# R1250GSA_Foglamp_Swith.net
KiCad netlist of a schematic drawn in Altium Designer
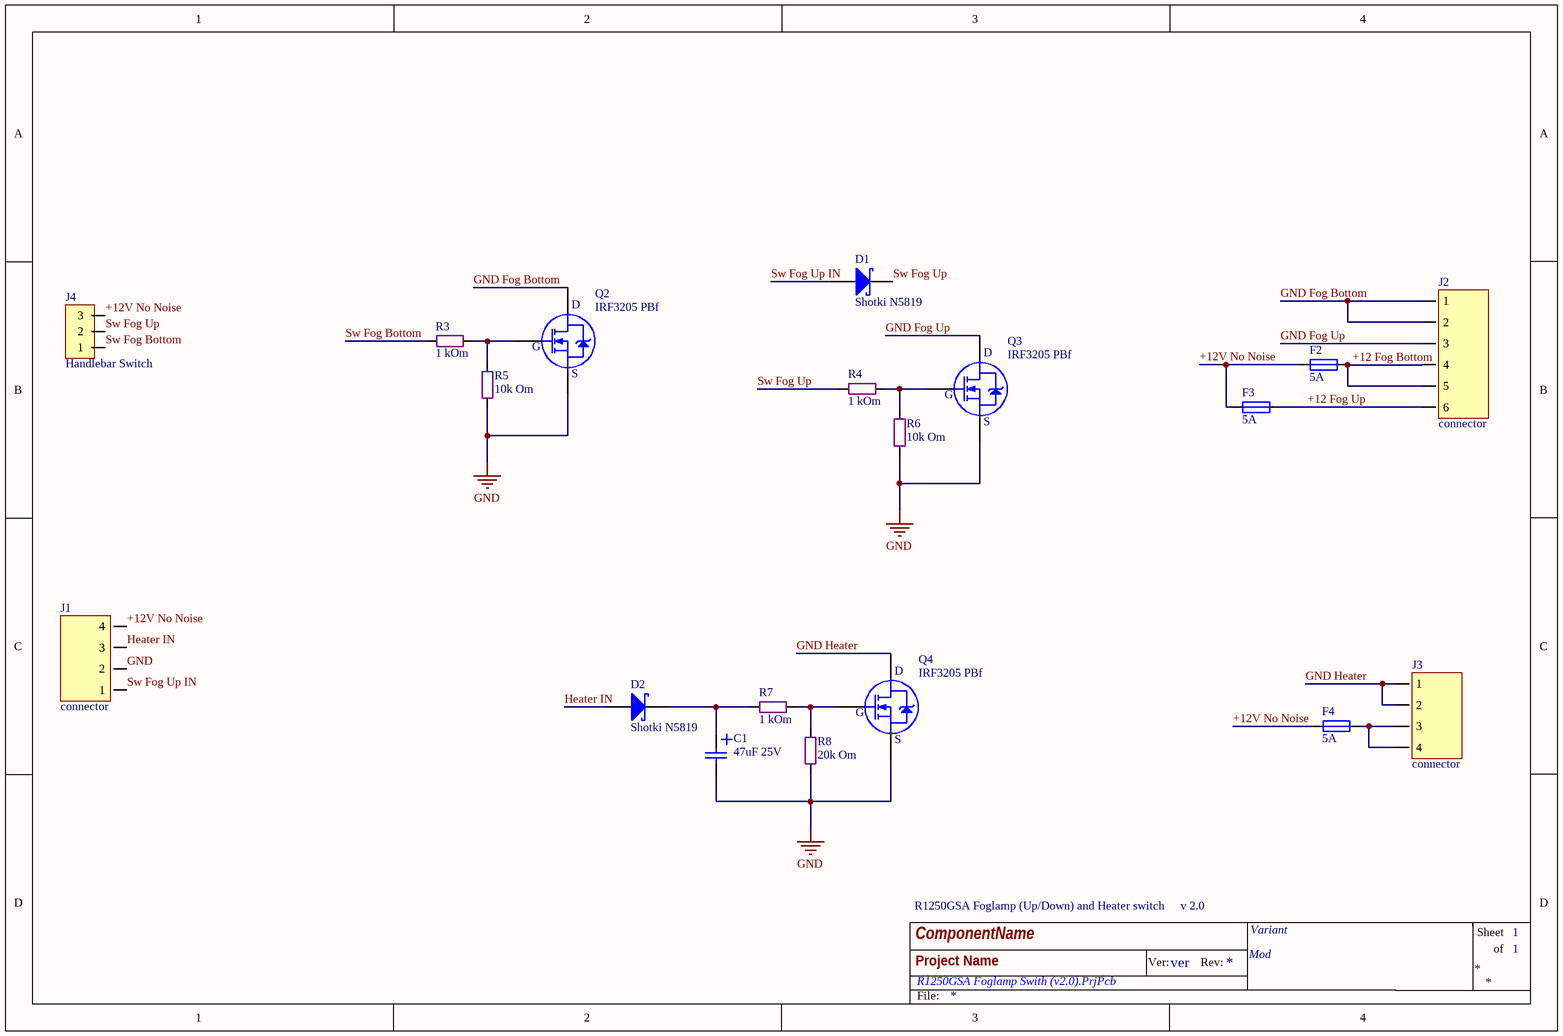
[diagram p0: R1250GSA Foglamp Swith (v2.0).SchDoc]

(export (version "E")
  (design (tool "Eeschema 10.0.6"))
  (components
    (comp (ref "C1")
      (value "47uF 25V")
      (footprint "Capacitor:Cap E p2mm D6.5xH11")
      (description "Capacitor")
      (libsource (lib "Capacitor") (part "Cap Elecrolitic"))
    )
    (comp (ref "D1")
      (value "Shotki N5819")
      (footprint "Diodes:Diode DO-41")
      (description "Shotki  Diode")
      (libsource (lib "Diodes") (part "D Shotki All"))
    )
    (comp (ref "D2")
      (value "Shotki N5819")
      (footprint "Diodes:Diode DO-41")
      (description "Shotki  Diode")
      (libsource (lib "Diodes") (part "D Shotki All"))
    )
    (comp (ref "F2")
      (value "5A")
      (footprint "PassiveComponents:Fuse RGE1100")
      (description "Round fuse")
      (libsource (lib "PassiveComponents") (part "Fuse"))
    )
    (comp (ref "F3")
      (value "5A")
      (footprint "PassiveComponents:Fuse RGE1100")
      (description "Round fuse")
      (libsource (lib "PassiveComponents") (part "Fuse"))
    )
    (comp (ref "F4")
      (value "5A")
      (footprint "PassiveComponents:Fuse RGE1100")
      (description "Round fuse")
      (libsource (lib "PassiveComponents") (part "Fuse"))
    )
    (comp (ref "J1")
      (value "connector")
      (footprint "Connector:Molex Mini-Fit Jr - 4Pin V")
      (description "Right, Dbl line, Female")
      (libsource (lib "") (part "Molex Mini-Fit Jr - 4 pin_1"))
    )
    (comp (ref "J2")
      (value "connector")
      (footprint "Connector:Molex Mini-Fit Jr - 6Pin V")
      (description "Right, Dbl line, Female")
      (libsource (lib "Connector") (part "Molex Mini-Fit Jr - 6 pin"))
    )
    (comp (ref "J3")
      (value "connector")
      (footprint "Connector:Molex Mini-Fit Jr - 4Pin V")
      (description "Right, Dbl line, Female")
      (libsource (lib "Connector") (part "Molex Mini-Fit Jr - 4 pin"))
    )
    (comp (ref "J4")
      (value "Handlebar Switch")
      (footprint "Connector:WF-3")
      (description "Standart Fan MB's Connector")
      (libsource (lib "Connector") (part "WF-3"))
    )
    (comp (ref "Q2")
      (value "IRF3205 PBf")
      (footprint "GeneralCases:TO220-2")
      (description "N-Channel 55V - 0.008Ω - 110A")
      (libsource (lib "Transistor") (part "IRF3205"))
    )
    (comp (ref "Q3")
      (value "IRF3205 PBf")
      (footprint "GeneralCases:TO220-2")
      (description "N-Channel 55V - 0.008Ω - 110A")
      (libsource (lib "Transistor") (part "IRF3205"))
    )
    (comp (ref "Q4")
      (value "IRF3205 PBf")
      (footprint "GeneralCases:TO220-2")
      (description "N-Channel 55V - 0.008Ω - 110A")
      (libsource (lib "Transistor") (part "IRF3205"))
    )
    (comp (ref "R3")
      (value "1 kOm")
      (footprint "PassiveComponents:SMD 0805 (2012)")
      (libsource (lib "PassiveComponents") (part "Res All Types"))
    )
    (comp (ref "R4")
      (value "1 kOm")
      (footprint "PassiveComponents:SMD 0805 (2012)")
      (libsource (lib "PassiveComponents") (part "Res All Types"))
    )
    (comp (ref "R5")
      (value "10k Om")
      (footprint "PassiveComponents:SMD 0805 (2012)")
      (libsource (lib "PassiveComponents") (part "Res All Types"))
    )
    (comp (ref "R6")
      (value "10k Om")
      (footprint "PassiveComponents:SMD 0805 (2012)")
      (libsource (lib "PassiveComponents") (part "Res All Types"))
    )
    (comp (ref "R7")
      (value "1 kOm")
      (footprint "PassiveComponents:SMD 0805 (2012)")
      (libsource (lib "PassiveComponents") (part "Res All Types"))
    )
    (comp (ref "R8")
      (value "20k Om")
      (footprint "PassiveComponents:SMD 0805 (2012)")
      (libsource (lib "PassiveComponents") (part "Res All Types"))
    )
  )
  (nets
    (net (code "1") (name "/+12 Fog Bottom") (class "Default")
      (node (ref "F2") (pin "2") (pinfunction "2_2") (pintype "passive"))
      (node (ref "J2") (pin "4") (pinfunction "4_4") (pintype "passive"))
      (node (ref "J2") (pin "5") (pinfunction "5_5") (pintype "passive"))
    )
    (net (code "2") (name "/+12 Fog Up") (class "Default")
      (node (ref "F3") (pin "2") (pinfunction "2_2") (pintype "passive"))
      (node (ref "J2") (pin "6") (pinfunction "6_6") (pintype "passive"))
    )
    (net (code "3") (name "/+12V No Noise") (class "Default")
      (node (ref "F2") (pin "1") (pinfunction "1_1") (pintype "passive"))
      (node (ref "F3") (pin "1") (pinfunction "1_1") (pintype "passive"))
      (node (ref "F4") (pin "1") (pinfunction "1_1") (pintype "passive"))
      (node (ref "J1") (pin "4") (pinfunction "4_4") (pintype "passive"))
      (node (ref "J4") (pin "3") (pinfunction "3_3") (pintype "passive"))
    )
    (net (code "4") (name "/GND Fog Bottom") (class "Default")
      (node (ref "J2") (pin "1") (pinfunction "1_1") (pintype "passive"))
      (node (ref "J2") (pin "2") (pinfunction "2_2") (pintype "passive"))
      (node (ref "Q2") (pin "2") (pinfunction "D_2") (pintype "passive"))
    )
    (net (code "5") (name "/GND Fog Up") (class "Default")
      (node (ref "J2") (pin "3") (pinfunction "3_3") (pintype "passive"))
      (node (ref "Q3") (pin "2") (pinfunction "D_2") (pintype "passive"))
    )
    (net (code "6") (name "/GND Heater") (class "Default")
      (node (ref "J3") (pin "1") (pinfunction "1_1") (pintype "passive"))
      (node (ref "J3") (pin "2") (pinfunction "2_2") (pintype "passive"))
      (node (ref "Q4") (pin "2") (pinfunction "D_2") (pintype "passive"))
    )
    (net (code "7") (name "/Heater IN") (class "Default")
      (node (ref "D2") (pin "A") (pinfunction "A_A") (pintype "passive"))
      (node (ref "J1") (pin "3") (pinfunction "3_3") (pintype "passive"))
    )
    (net (code "8") (name "/Sw Fog Bottom") (class "Default")
      (node (ref "J4") (pin "1") (pinfunction "1_1") (pintype "passive"))
      (node (ref "R3") (pin "1") (pinfunction "1_1") (pintype "passive"))
    )
    (net (code "9") (name "/Sw Fog Up") (class "Default")
      (node (ref "D1") (pin "K") (pinfunction "K_K") (pintype "passive"))
      (node (ref "J4") (pin "2") (pinfunction "2_2") (pintype "passive"))
      (node (ref "R4") (pin "1") (pinfunction "1_1") (pintype "passive"))
    )
    (net (code "10") (name "/Sw Fog Up IN") (class "Default")
      (node (ref "D1") (pin "A") (pinfunction "A_A") (pintype "passive"))
      (node (ref "J1") (pin "1") (pinfunction "1_1") (pintype "passive"))
    )
    (net (code "11") (name "GND") (class "Default")
      (node (ref "C1") (pin "2") (pinfunction "2_2") (pintype "passive"))
      (node (ref "J1") (pin "2") (pinfunction "2_2") (pintype "passive"))
      (node (ref "Q2") (pin "3") (pinfunction "S_3") (pintype "passive"))
      (node (ref "Q3") (pin "3") (pinfunction "S_3") (pintype "passive"))
      (node (ref "Q4") (pin "3") (pinfunction "S_3") (pintype "passive"))
      (node (ref "R5") (pin "1") (pinfunction "1_1") (pintype "passive"))
      (node (ref "R6") (pin "1") (pinfunction "1_1") (pintype "passive"))
      (node (ref "R8") (pin "1") (pinfunction "1_1") (pintype "passive"))
    )
    (net (code "12") (name "Net-(C1-Pad1)") (class "Default")
      (node (ref "C1") (pin "1") (pinfunction "1_1") (pintype "passive"))
      (node (ref "D2") (pin "K") (pinfunction "K_K") (pintype "passive"))
      (node (ref "R7") (pin "1") (pinfunction "1_1") (pintype "passive"))
    )
    (net (code "13") (name "Net-(F4-Pad2)") (class "Default")
      (node (ref "F4") (pin "2") (pinfunction "2_2") (pintype "passive"))
      (node (ref "J3") (pin "3") (pinfunction "3_3") (pintype "passive"))
      (node (ref "J3") (pin "4") (pinfunction "4_4") (pintype "passive"))
    )
    (net (code "14") (name "Net-(Q2-G)") (class "Default")
      (node (ref "Q2") (pin "1") (pinfunction "G_1") (pintype "passive"))
      (node (ref "R3") (pin "2") (pinfunction "2_2") (pintype "passive"))
      (node (ref "R5") (pin "2") (pinfunction "2_2") (pintype "passive"))
    )
    (net (code "15") (name "Net-(Q3-G)") (class "Default")
      (node (ref "Q3") (pin "1") (pinfunction "G_1") (pintype "passive"))
      (node (ref "R4") (pin "2") (pinfunction "2_2") (pintype "passive"))
      (node (ref "R6") (pin "2") (pinfunction "2_2") (pintype "passive"))
    )
    (net (code "16") (name "Net-(Q4-G)") (class "Default")
      (node (ref "Q4") (pin "1") (pinfunction "G_1") (pintype "passive"))
      (node (ref "R7") (pin "2") (pinfunction "2_2") (pintype "passive"))
      (node (ref "R8") (pin "2") (pinfunction "2_2") (pintype "passive"))
    )
  )
)
